# HBridge_GW.net
KiCad netlist of a schematic drawn in Altium Designer
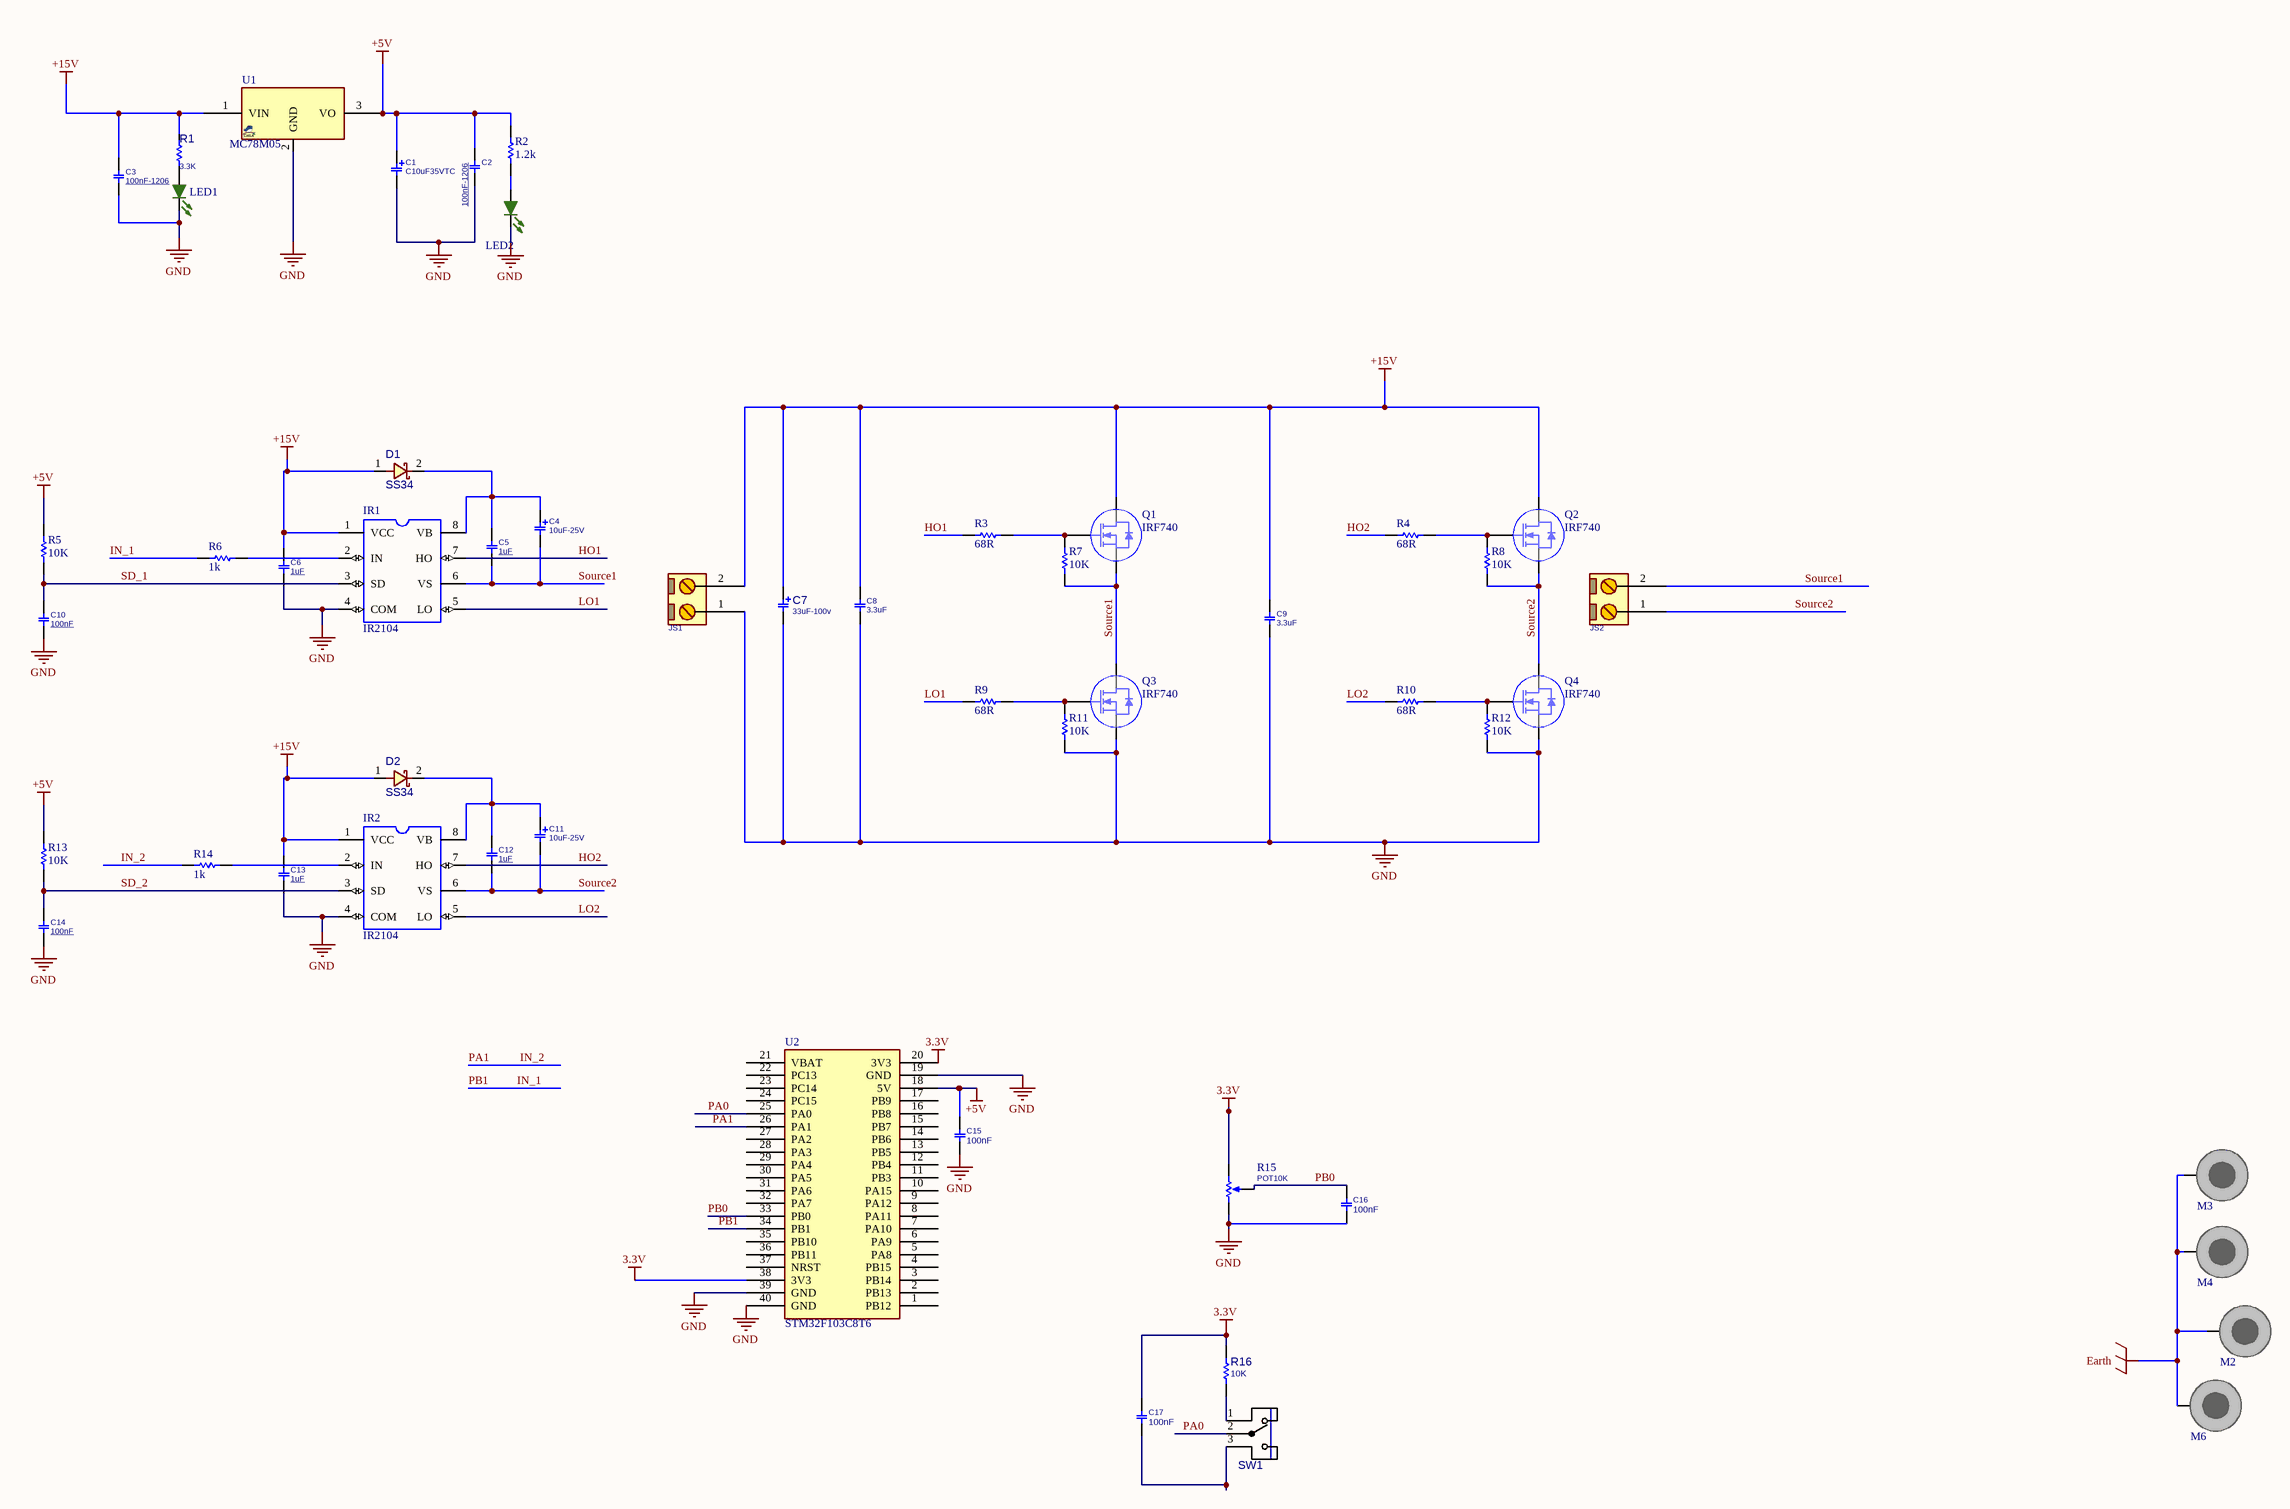
[diagram p0: HBridge_GW.SchDoc]

(export (version "E")
  (design (tool "Eeschema 10.0.6"))
  (components
    (comp (ref "C1")
      (value "C10uF35VTC")
      (footprint "C_TN_6032")
      (description "CAP, SMD, TAN,")
      (libsource (lib "passive_smd") (part "CAP_SMD_TAN_6032"))
    )
    (comp (ref "C2")
      (value "100nF-1206")
      (footprint "C1206")
      (description "CAP, MLCC, -F, -V, MATERIAL, -%, 0201")
      (fields (field (name "MANF_P#") "MANF_PART#"))
      (libsource (lib "passive_smd") (part "CAP_SMD_MLCC_1206"))
    )
    (comp (ref "C3")
      (value "100nF-1206")
      (footprint "C1206")
      (description "CAP, MLCC, -F, -V, MATERIAL, -%, 0201")
      (fields (field (name "MANF_P#") "MANF_PART#"))
      (libsource (lib "passive_smd") (part "CAP_SMD_MLCC_1206"))
    )
    (comp (ref "C4")
      (value "10uF-25V")
      (footprint "C_TN_3528")
      (description "CAP, SMD, TAN,")
      (libsource (lib "passive") (part "CAP_SMD_TAN"))
    )
    (comp (ref "C5")
      (value "1uF")
      (footprint "C1206")
      (description "CAP, MLCC, 1nF, 50V, C0G, 10%, 0402")
      (fields (field (name "MANF_P#") "MANF_PART#") (field (name "MANF") "Murata"))
      (libsource (lib "passive_smd") (part "CAP_SMD_MLCC"))
    )
    (comp (ref "C6")
      (value "1uF")
      (footprint "C1206")
      (description "CAP, MLCC, 1nF, 50V, C0G, 10%, 0402")
      (fields (field (name "MANF_P#") "MANF_PART#") (field (name "MANF") "Murata"))
      (libsource (lib "passive_smd") (part "CAP_SMD_MLCC"))
    )
    (comp (ref "C7")
      (value "33uF-100v")
      (footprint "C_EL_8X12")
      (description "CAP, THD, ELEC, 330uF, 25V")
      (fields (field (name "MANF_P#") "EEE-1EA331UP") (field (name "MANF") "PANASONIC"))
      (libsource (lib "CapElect_passive") (part "CAP_THD_EL_330u25V"))
    )
    (comp (ref "C8")
      (value "3.3uF")
      (footprint "C_PLY_13X5")
      (description "CAP, FILM, 10nF, 630V")
      (fields (field (name "MANF_P#") "MANF_PART#") (field (name "MANF") "MANF"))
      (libsource (lib "CapFilm_polyester_passive") (part "CAP_THD_FILMPLY_10N630V"))
    )
    (comp (ref "C9")
      (value "3.3uF")
      (footprint "C_PLY_13X5")
      (description "CAP, FILM, 10nF, 630V")
      (fields (field (name "MANF_P#") "MANF_PART#") (field (name "MANF") "MANF"))
      (libsource (lib "CapFilm_polyester_passive") (part "CAP_THD_FILMPLY_10N630V"))
    )
    (comp (ref "C10")
      (value "100nF")
      (footprint "C1206")
      (description "CAP, MLCC, 1nF, 50V, C0G, 10%, 0402")
      (fields (field (name "MANF_P#") "MANF_PART#") (field (name "MANF") "Murata"))
      (libsource (lib "passive_smd") (part "CAP_SMD_MLCC"))
    )
    (comp (ref "C11")
      (value "10uF-25V")
      (footprint "C_TN_3528")
      (description "CAP, SMD, TAN,")
      (libsource (lib "passive") (part "CAP_SMD_TAN"))
    )
    (comp (ref "C12")
      (value "1uF")
      (footprint "C1206")
      (description "CAP, MLCC, 1nF, 50V, C0G, 10%, 0402")
      (fields (field (name "MANF_P#") "MANF_PART#") (field (name "MANF") "Murata"))
      (libsource (lib "passive_smd") (part "CAP_SMD_MLCC"))
    )
    (comp (ref "C13")
      (value "1uF")
      (footprint "C1206")
      (description "CAP, MLCC, 1nF, 50V, C0G, 10%, 0402")
      (fields (field (name "MANF_P#") "MANF_PART#") (field (name "MANF") "Murata"))
      (libsource (lib "passive_smd") (part "CAP_SMD_MLCC"))
    )
    (comp (ref "C14")
      (value "100nF")
      (footprint "C1206")
      (description "CAP, MLCC, 1nF, 50V, C0G, 10%, 0402")
      (fields (field (name "MANF_P#") "MANF_PART#") (field (name "MANF") "Murata"))
      (libsource (lib "passive_smd") (part "CAP_SMD_MLCC"))
    )
    (comp (ref "C15")
      (value "100nF")
      (footprint "C1206")
      (description "CAP, MLCC")
      (fields (field (name "MANF_P#") "MANF_PART#"))
      (libsource (lib "passive_smd") (part "CAP_SMD_MLCC_1206"))
    )
    (comp (ref "C16")
      (value "100nF")
      (footprint "C1206")
      (description "CAP, MLCC")
      (fields (field (name "MANF_P#") "MANF_PART#"))
      (libsource (lib "passive_smd") (part "CAP_SMD_MLCC_1206"))
    )
    (comp (ref "C17")
      (value "100nF")
      (footprint "C1206")
      (description "CAP, MLCC")
      (fields (field (name "MANF_P#") "MANF_PART#"))
      (libsource (lib "passive_smd") (part "CAP_SMD_MLCC_1206"))
    )
    (comp (ref "D1")
      (value "SS34")
      (footprint "D_SMB")
      (description "DIODE, SCHOTTKY, 40V, 3A")
      (fields (field (name "MANF") "VISHAY"))
      (libsource (lib "diode") (part "DIODE_SMD_SCHOTTKY_SS34"))
    )
    (comp (ref "D2")
      (value "SS34")
      (footprint "D_SMB")
      (description "DIODE, SCHOTTKY, 40V, 3A")
      (fields (field (name "MANF") "VISHAY"))
      (libsource (lib "diode") (part "DIODE_SMD_SCHOTTKY_SS34"))
    )
    (comp (ref "IR1")
      (value "IR2104")
      (footprint "IR2104S")
      (description "Half-Bridge Gate Driver IC Non-Inverting")
      (fields (field (name "MP") "IR2104S") (field (name "MF") "Infineon Technologies"))
      (libsource (lib "IR2104S") (part "IR2104S"))
    )
    (comp (ref "IR2")
      (value "IR2104")
      (footprint "IR2104S")
      (description "Half-Bridge Gate Driver IC Non-Inverting")
      (fields (field (name "MP") "IR2104S") (field (name "MF") "Infineon Technologies"))
      (libsource (lib "IR2104S") (part "IR2104S"))
    )
    (comp (ref "JS1")
      (value "24V")
      (footprint "MSTB_2")
      (description "CONN, PHOENIX MSTB, 5-G, 5.08mm pitch")
      (libsource (lib "conn_power_terminalB") (part "CONN_MSTB_2"))
    )
    (comp (ref "JS2")
      (value "24V")
      (footprint "MSTB_2")
      (description "CONN, PHOENIX MSTB, 5-G, 5.08mm pitch")
      (libsource (lib "conn_power_terminalB") (part "CONN_MSTB_2"))
    )
    (comp (ref "LED1")
      (value "LED SMD 1206 GREEN")
      (footprint "IE_BuckProject:LED 1206 @")
      (libsource (lib "Schlib1") (part "LED SMD 1206 GREEN"))
    )
    (comp (ref "LED2")
      (value "LED SMD 1206 GREEN")
      (footprint "IE_BuckProject:LED 1206 @")
      (libsource (lib "Schlib1") (part "LED SMD 1206 GREEN"))
    )
    (comp (ref "M2")
      (value "DNP/MH")
      (footprint "SCMH_M3")
      (description "SCREW mouting, M3, 3.0mm diameter and 6.0mm PanHead")
      (libsource (lib "mech_mountingHole") (part "SCMH_M3"))
    )
    (comp (ref "M3")
      (value "DNP/MH")
      (footprint "SCMH_M3")
      (description "SCREW mouting, M3, 3.0mm diameter and 6.0mm PanHead")
      (libsource (lib "mech_mountingHole") (part "SCMH_M3"))
    )
    (comp (ref "M4")
      (value "DNP/MH")
      (footprint "SCMH_M3")
      (description "SCREW mouting, M3, 3.0mm diameter and 6.0mm PanHead")
      (libsource (lib "mech_mountingHole") (part "SCMH_M3"))
    )
    (comp (ref "M6")
      (value "DNP/MH")
      (footprint "SCMH_M3")
      (description "SCREW mouting, M3, 3.0mm diameter and 6.0mm PanHead")
      (libsource (lib "mech_mountingHole") (part "SCMH_M3"))
    )
    (comp (ref "Q1")
      (value "IRF740")
      (footprint "TO-220 AB")
      (description "MOSFET N-CH 400V 10A TO-220AB")
      (fields (field (name "PUBLISHER") "Abbas Basereh"))
      (libsource (lib "General 1") (part "IRF740"))
    )
    (comp (ref "Q2")
      (value "IRF740")
      (footprint "TO-220 AB")
      (description "MOSFET N-CH 400V 10A TO-220AB")
      (fields (field (name "PUBLISHER") "Abbas Basereh"))
      (libsource (lib "General 1") (part "IRF740"))
    )
    (comp (ref "Q3")
      (value "IRF740")
      (footprint "TO-220 AB")
      (description "MOSFET N-CH 400V 10A TO-220AB")
      (fields (field (name "PUBLISHER") "Abbas Basereh"))
      (libsource (lib "General 1") (part "IRF740"))
    )
    (comp (ref "Q4")
      (value "IRF740")
      (footprint "TO-220 AB")
      (description "MOSFET N-CH 400V 10A TO-220AB")
      (fields (field (name "PUBLISHER") "Abbas Basereh"))
      (libsource (lib "General 1") (part "IRF740"))
    )
    (comp (ref "R1")
      (value "3.3K")
      (footprint "RESC4817X04N")
      (description "RESISTOR, SMD")
      (fields (field (name "Comment") "RES_SMD") (field (name "DESIGNER") "ahmadi"))
      (libsource (lib "Schlib1") (part "RES_SMD"))
    )
    (comp (ref "R2")
      (value "1.2k")
      (footprint "RESC4817X04N")
      (description "RES 1206")
      (fields (field (name "DESIGNER") "Abbas Basereh"))
      (libsource (lib "2017AbbasBasereh9365731239 -ver1") (part "RES 1206 0.25W"))
    )
    (comp (ref "R3")
      (value "68R")
      (footprint "RESC4817X04N")
      (description "RES 1206")
      (fields (field (name "DESIGNER") "Abbas Basereh"))
      (libsource (lib "2017AbbasBasereh9365731239 -ver1") (part "RES 1206 0.25W"))
    )
    (comp (ref "R4")
      (value "68R")
      (footprint "RESC4817X04N")
      (description "RES 1206")
      (fields (field (name "DESIGNER") "Abbas Basereh"))
      (libsource (lib "2017AbbasBasereh9365731239 -ver1") (part "RES 1206 0.25W"))
    )
    (comp (ref "R5")
      (value "10K")
      (footprint "RESC4817X04N")
      (description "RES 1206")
      (fields (field (name "DESIGNER") "Abbas Basereh"))
      (libsource (lib "2017AbbasBasereh9365731239 -ver1") (part "RES 1206 0.25W"))
    )
    (comp (ref "R6")
      (value "1k")
      (footprint "RESC4817X04N")
      (description "RES 1206")
      (fields (field (name "DESIGNER") "Abbas Basereh"))
      (libsource (lib "2017AbbasBasereh9365731239 -ver1") (part "RES 1206 0.25W"))
    )
    (comp (ref "R7")
      (value "10K")
      (footprint "RESC4817X04N")
      (description "RES 1206")
      (fields (field (name "DESIGNER") "Abbas Basereh"))
      (libsource (lib "2017AbbasBasereh9365731239 -ver1") (part "RES 1206 0.25W"))
    )
    (comp (ref "R8")
      (value "10K")
      (footprint "RESC4817X04N")
      (description "RES 1206")
      (fields (field (name "DESIGNER") "Abbas Basereh"))
      (libsource (lib "2017AbbasBasereh9365731239 -ver1") (part "RES 1206 0.25W"))
    )
    (comp (ref "R9")
      (value "68R")
      (footprint "RESC4817X04N")
      (description "RES 1206")
      (fields (field (name "DESIGNER") "Abbas Basereh"))
      (libsource (lib "2017AbbasBasereh9365731239 -ver1") (part "RES 1206 0.25W"))
    )
    (comp (ref "R10")
      (value "68R")
      (footprint "RESC4817X04N")
      (description "RES 1206")
      (fields (field (name "DESIGNER") "Abbas Basereh"))
      (libsource (lib "2017AbbasBasereh9365731239 -ver1") (part "RES 1206 0.25W"))
    )
    (comp (ref "R11")
      (value "10K")
      (footprint "RESC4817X04N")
      (description "RES 1206")
      (fields (field (name "DESIGNER") "Abbas Basereh"))
      (libsource (lib "2017AbbasBasereh9365731239 -ver1") (part "RES 1206 0.25W"))
    )
    (comp (ref "R12")
      (value "10K")
      (footprint "RESC4817X04N")
      (description "RES 1206")
      (fields (field (name "DESIGNER") "Abbas Basereh"))
      (libsource (lib "2017AbbasBasereh9365731239 -ver1") (part "RES 1206 0.25W"))
    )
    (comp (ref "R13")
      (value "10K")
      (footprint "RESC4817X04N")
      (description "RES 1206")
      (fields (field (name "DESIGNER") "Abbas Basereh"))
      (libsource (lib "2017AbbasBasereh9365731239 -ver1") (part "RES 1206 0.25W"))
    )
    (comp (ref "R14")
      (value "1k")
      (footprint "RESC4817X04N")
      (description "RES 1206")
      (fields (field (name "DESIGNER") "Abbas Basereh"))
      (libsource (lib "2017AbbasBasereh9365731239 -ver1") (part "RES 1206 0.25W"))
    )
    (comp (ref "R15")
      (value "POT10K")
      (footprint "VOL_R")
      (description "RESISTOR, THD, Potentiometer Volume")
      (libsource (lib "resistor_pot_trimmer") (part "RES_THD_POT_VOLUME"))
    )
    (comp (ref "R16")
      (value "10K")
      (footprint "R1206")
      (description "RESISTOR, SMD")
      (libsource (lib "passive_smd") (part "RES_SMD_1206"))
    )
    (comp (ref "SW1")
      (value "ToggleSwitch")
      (footprint "SWTOG_SPDT_S_7101SY")
      (description "SWITCH, TOGGLE, SPDT, THD")
      (fields (field (name "MANF") "C&K") (field (name "MANF_PART#") "7101SYZBE"))
      (libsource (lib "switch_toggle") (part "SWTOG_SPDT_S_7101SY"))
    )
    (comp (ref "U1")
      (value "MC78M05")
      (footprint "TO220_3")
      (description "REG, Linear, Fixed, 5v, 1.5A, TO-220")
      (fields (field (name "MANF") "TI, ST, FAIRCHILD, ON, NJR, TS"))
      (libsource (lib "pwr_reg_linear_78xx79xx") (part "VREG_78M05_TO220"))
    )
    (comp (ref "U2")
      (value "STM32F103C8T6")
      (footprint "Stm32 BluePill")
      (description "Designed By @Alixahedi")
      (libsource (lib "Stm32 Blue Pill") (part "BluePill"))
    )
  )
  (nets
    (net (code "1") (name "+5V") (class "Default")
      (node (ref "C1") (pin "1") (pinfunction "1_1") (pintype "passive"))
      (node (ref "C15") (pin "2") (pinfunction "2_2") (pintype "passive"))
      (node (ref "C2") (pin "1") (pinfunction "1_1") (pintype "passive"))
      (node (ref "R13") (pin "2") (pinfunction "2_2") (pintype "passive"))
      (node (ref "R2") (pin "1") (pinfunction "1_1") (pintype "passive"))
      (node (ref "R5") (pin "2") (pinfunction "2_2") (pintype "passive"))
      (node (ref "U1") (pin "3") (pinfunction "VO_3") (pintype "passive"))
      (node (ref "U2") (pin "18") (pinfunction "5V_18") (pintype "passive"))
    )
    (net (code "2") (name "+15V") (class "Default")
      (node (ref "C13") (pin "2") (pinfunction "2_2") (pintype "passive"))
      (node (ref "C3") (pin "1") (pinfunction "1_1") (pintype "passive"))
      (node (ref "C6") (pin "2") (pinfunction "2_2") (pintype "passive"))
      (node (ref "C7") (pin "1") (pinfunction "1_1") (pintype "passive"))
      (node (ref "C8") (pin "2") (pinfunction "2_2") (pintype "passive"))
      (node (ref "C9") (pin "2") (pinfunction "2_2") (pintype "passive"))
      (node (ref "D1") (pin "1") (pinfunction "1_1") (pintype "passive"))
      (node (ref "D2") (pin "1") (pinfunction "1_1") (pintype "passive"))
      (node (ref "IR1") (pin "1") (pinfunction "VCC_1") (pintype "power_in"))
      (node (ref "IR2") (pin "1") (pinfunction "VCC_1") (pintype "power_in"))
      (node (ref "JS1") (pin "2") (pinfunction "2_2") (pintype "passive"))
      (node (ref "Q1") (pin "2") (pinfunction "D_2") (pintype "power_in"))
      (node (ref "Q2") (pin "2") (pinfunction "D_2") (pintype "power_in"))
      (node (ref "R1") (pin "1") (pinfunction "1_1") (pintype "passive"))
      (node (ref "U1") (pin "1") (pinfunction "VIN_1") (pintype "passive"))
    )
    (net (code "3") (name "/HO1") (class "Default")
      (node (ref "IR1") (pin "7") (pinfunction "HO_7") (pintype "bidirectional"))
      (node (ref "R3") (pin "2") (pinfunction "2_2") (pintype "passive"))
    )
    (net (code "4") (name "/HO2") (class "Default")
      (node (ref "IR2") (pin "7") (pinfunction "HO_7") (pintype "bidirectional"))
      (node (ref "R4") (pin "2") (pinfunction "2_2") (pintype "passive"))
    )
    (net (code "5") (name "/IN_1") (class "Default")
      (node (ref "R6") (pin "2") (pinfunction "2_2") (pintype "passive"))
      (node (ref "U2") (pin "34") (pinfunction "PB1_34") (pintype "passive"))
    )
    (net (code "6") (name "/IN_2") (class "Default")
      (node (ref "R14") (pin "2") (pinfunction "2_2") (pintype "passive"))
      (node (ref "U2") (pin "26") (pinfunction "PA1_26") (pintype "passive"))
    )
    (net (code "7") (name "/LO1") (class "Default")
      (node (ref "IR1") (pin "5") (pinfunction "LO_5") (pintype "bidirectional"))
      (node (ref "R9") (pin "2") (pinfunction "2_2") (pintype "passive"))
    )
    (net (code "8") (name "/LO2") (class "Default")
      (node (ref "IR2") (pin "5") (pinfunction "LO_5") (pintype "bidirectional"))
      (node (ref "R10") (pin "2") (pinfunction "2_2") (pintype "passive"))
    )
    (net (code "9") (name "/PA0") (class "Default")
      (node (ref "SW1") (pin "2") (pinfunction "COM_2") (pintype "passive"))
      (node (ref "U2") (pin "25") (pinfunction "PA0_25") (pintype "passive"))
    )
    (net (code "10") (name "/PB0") (class "Default")
      (node (ref "C16") (pin "2") (pinfunction "2_2") (pintype "passive"))
      (node (ref "R15") (pin "2") (pinfunction "TAP_2") (pintype "passive"))
      (node (ref "U2") (pin "33") (pinfunction "PB0_33") (pintype "passive"))
    )
    (net (code "11") (name "/SD_1") (class "Default")
      (node (ref "C10") (pin "2") (pinfunction "2_2") (pintype "passive"))
      (node (ref "IR1") (pin "3") (pinfunction "SD_3") (pintype "bidirectional"))
      (node (ref "R5") (pin "1") (pinfunction "1_1") (pintype "passive"))
    )
    (net (code "12") (name "/SD_2") (class "Default")
      (node (ref "C14") (pin "2") (pinfunction "2_2") (pintype "passive"))
      (node (ref "IR2") (pin "3") (pinfunction "SD_3") (pintype "bidirectional"))
      (node (ref "R13") (pin "1") (pinfunction "1_1") (pintype "passive"))
    )
    (net (code "13") (name "/Source1") (class "Default")
      (node (ref "C4") (pin "2") (pinfunction "2_2") (pintype "passive"))
      (node (ref "C5") (pin "1") (pinfunction "1_1") (pintype "passive"))
      (node (ref "IR1") (pin "6") (pinfunction "VS_6") (pintype "power_in"))
      (node (ref "JS2") (pin "2") (pinfunction "2_2") (pintype "passive"))
      (node (ref "Q1") (pin "3") (pinfunction "S_3") (pintype "power_in"))
      (node (ref "Q3") (pin "2") (pinfunction "D_2") (pintype "power_in"))
      (node (ref "R7") (pin "1") (pinfunction "1_1") (pintype "passive"))
    )
    (net (code "14") (name "/Source2") (class "Default")
      (node (ref "C11") (pin "2") (pinfunction "2_2") (pintype "passive"))
      (node (ref "C12") (pin "1") (pinfunction "1_1") (pintype "passive"))
      (node (ref "IR2") (pin "6") (pinfunction "VS_6") (pintype "power_in"))
      (node (ref "JS2") (pin "1") (pinfunction "1_1") (pintype "passive"))
      (node (ref "Q2") (pin "3") (pinfunction "S_3") (pintype "power_in"))
      (node (ref "Q4") (pin "2") (pinfunction "D_2") (pintype "power_in"))
      (node (ref "R8") (pin "1") (pinfunction "1_1") (pintype "passive"))
    )
    (net (code "15") (name "3.3V") (class "Default")
      (node (ref "C17") (pin "1") (pinfunction "1_1") (pintype "passive"))
      (node (ref "R15") (pin "3") (pinfunction "BOT_3") (pintype "passive"))
      (node (ref "R16") (pin "2") (pinfunction "2_2") (pintype "passive"))
      (node (ref "U2") (pin "20") (pinfunction "3V3_20") (pintype "passive"))
      (node (ref "U2") (pin "38") (pinfunction "3V3_38") (pintype "passive"))
    )
    (net (code "16") (name "Earth") (class "Default")
      (node (ref "M2") (pin "1") (pinfunction "1_1") (pintype "passive"))
      (node (ref "M3") (pin "1") (pinfunction "1_1") (pintype "passive"))
      (node (ref "M4") (pin "1") (pinfunction "1_1") (pintype "passive"))
      (node (ref "M6") (pin "1") (pinfunction "1_1") (pintype "passive"))
    )
    (net (code "17") (name "GND") (class "Default")
      (node (ref "C1") (pin "2") (pinfunction "2_2") (pintype "passive"))
      (node (ref "C10") (pin "1") (pinfunction "1_1") (pintype "passive"))
      (node (ref "C13") (pin "1") (pinfunction "1_1") (pintype "passive"))
      (node (ref "C14") (pin "1") (pinfunction "1_1") (pintype "passive"))
      (node (ref "C15") (pin "1") (pinfunction "1_1") (pintype "passive"))
      (node (ref "C16") (pin "1") (pinfunction "1_1") (pintype "passive"))
      (node (ref "C2") (pin "2") (pinfunction "2_2") (pintype "passive"))
      (node (ref "C3") (pin "2") (pinfunction "2_2") (pintype "passive"))
      (node (ref "C6") (pin "1") (pinfunction "1_1") (pintype "passive"))
      (node (ref "C7") (pin "2") (pinfunction "2_2") (pintype "passive"))
      (node (ref "C8") (pin "1") (pinfunction "1_1") (pintype "passive"))
      (node (ref "C9") (pin "1") (pinfunction "1_1") (pintype "passive"))
      (node (ref "IR1") (pin "4") (pinfunction "COM_4") (pintype "bidirectional"))
      (node (ref "IR2") (pin "4") (pinfunction "COM_4") (pintype "bidirectional"))
      (node (ref "JS1") (pin "1") (pinfunction "1_1") (pintype "passive"))
      (node (ref "LED1") (pin "2") (pinfunction "K_2") (pintype "passive"))
      (node (ref "LED2") (pin "2") (pinfunction "K_2") (pintype "passive"))
      (node (ref "Q3") (pin "3") (pinfunction "S_3") (pintype "power_in"))
      (node (ref "Q4") (pin "3") (pinfunction "S_3") (pintype "power_in"))
      (node (ref "R11") (pin "1") (pinfunction "1_1") (pintype "passive"))
      (node (ref "R12") (pin "1") (pinfunction "1_1") (pintype "passive"))
      (node (ref "R15") (pin "1") (pinfunction "TOP_1") (pintype "passive"))
      (node (ref "U1") (pin "2") (pinfunction "GND_2") (pintype "passive"))
      (node (ref "U2") (pin "19") (pinfunction "GND_19") (pintype "passive"))
      (node (ref "U2") (pin "39") (pinfunction "GND_39") (pintype "passive"))
      (node (ref "U2") (pin "40") (pinfunction "GND_40") (pintype "passive"))
    )
    (net (code "18") (name "Net-(IR1-IN)") (class "Default")
      (node (ref "IR1") (pin "2") (pinfunction "IN_2") (pintype "bidirectional"))
      (node (ref "R6") (pin "1") (pinfunction "1_1") (pintype "passive"))
    )
    (net (code "19") (name "Net-(IR1-VB)") (class "Default")
      (node (ref "C4") (pin "1") (pinfunction "1_1") (pintype "passive"))
      (node (ref "C5") (pin "2") (pinfunction "2_2") (pintype "passive"))
      (node (ref "D1") (pin "2") (pinfunction "2_2") (pintype "passive"))
      (node (ref "IR1") (pin "8") (pinfunction "VB_8") (pintype "power_in"))
    )
    (net (code "20") (name "Net-(IR2-IN)") (class "Default")
      (node (ref "IR2") (pin "2") (pinfunction "IN_2") (pintype "bidirectional"))
      (node (ref "R14") (pin "1") (pinfunction "1_1") (pintype "passive"))
    )
    (net (code "21") (name "Net-(IR2-VB)") (class "Default")
      (node (ref "C11") (pin "1") (pinfunction "1_1") (pintype "passive"))
      (node (ref "C12") (pin "2") (pinfunction "2_2") (pintype "passive"))
      (node (ref "D2") (pin "2") (pinfunction "2_2") (pintype "passive"))
      (node (ref "IR2") (pin "8") (pinfunction "VB_8") (pintype "power_in"))
    )
    (net (code "22") (name "Net-(LED1-A)") (class "Default")
      (node (ref "LED1") (pin "1") (pinfunction "A_1") (pintype "passive"))
      (node (ref "R1") (pin "2") (pinfunction "2_2") (pintype "passive"))
    )
    (net (code "23") (name "Net-(LED2-A)") (class "Default")
      (node (ref "LED2") (pin "1") (pinfunction "A_1") (pintype "passive"))
      (node (ref "R2") (pin "2") (pinfunction "2_2") (pintype "passive"))
    )
    (net (code "24") (name "Net-(Q1-G)") (class "Default")
      (node (ref "Q1") (pin "1") (pinfunction "G_1") (pintype "passive"))
      (node (ref "R3") (pin "1") (pinfunction "1_1") (pintype "passive"))
      (node (ref "R7") (pin "2") (pinfunction "2_2") (pintype "passive"))
    )
    (net (code "25") (name "Net-(Q2-G)") (class "Default")
      (node (ref "Q2") (pin "1") (pinfunction "G_1") (pintype "passive"))
      (node (ref "R4") (pin "1") (pinfunction "1_1") (pintype "passive"))
      (node (ref "R8") (pin "2") (pinfunction "2_2") (pintype "passive"))
    )
    (net (code "26") (name "Net-(Q3-G)") (class "Default")
      (node (ref "Q3") (pin "1") (pinfunction "G_1") (pintype "passive"))
      (node (ref "R11") (pin "2") (pinfunction "2_2") (pintype "passive"))
      (node (ref "R9") (pin "1") (pinfunction "1_1") (pintype "passive"))
    )
    (net (code "27") (name "Net-(Q4-G)") (class "Default")
      (node (ref "Q4") (pin "1") (pinfunction "G_1") (pintype "passive"))
      (node (ref "R10") (pin "1") (pinfunction "1_1") (pintype "passive"))
      (node (ref "R12") (pin "2") (pinfunction "2_2") (pintype "passive"))
    )
    (net (code "28") (name "Net-(SW1-T1)") (class "Default")
      (node (ref "R16") (pin "1") (pinfunction "1_1") (pintype "passive"))
      (node (ref "SW1") (pin "1") (pinfunction "T1_1") (pintype "passive"))
    )
    (net (code "29") (name "Net-(SW1-T2)") (class "Default")
      (node (ref "C17") (pin "2") (pinfunction "2_2") (pintype "passive"))
      (node (ref "SW1") (pin "3") (pinfunction "T2_3") (pintype "passive"))
    )
    (net (code "30") (name "unconnected-(U2-NRST-Pad37)") (class "Default")
      (node (ref "U2") (pin "37") (pinfunction "NRST_37") (pintype "passive"))
    )
    (net (code "31") (name "unconnected-(U2-PA2-Pad27)") (class "Default")
      (node (ref "U2") (pin "27") (pinfunction "PA2_27") (pintype "passive"))
    )
    (net (code "32") (name "unconnected-(U2-PA3-Pad28)") (class "Default")
      (node (ref "U2") (pin "28") (pinfunction "PA3_28") (pintype "passive"))
    )
    (net (code "33") (name "unconnected-(U2-PA4-Pad29)") (class "Default")
      (node (ref "U2") (pin "29") (pinfunction "PA4_29") (pintype "passive"))
    )
    (net (code "34") (name "unconnected-(U2-PA5-Pad30)") (class "Default")
      (node (ref "U2") (pin "30") (pinfunction "PA5_30") (pintype "passive"))
    )
    (net (code "35") (name "unconnected-(U2-PA6-Pad31)") (class "Default")
      (node (ref "U2") (pin "31") (pinfunction "PA6_31") (pintype "passive"))
    )
    (net (code "36") (name "unconnected-(U2-PA7-Pad32)") (class "Default")
      (node (ref "U2") (pin "32") (pinfunction "PA7_32") (pintype "passive"))
    )
    (net (code "37") (name "unconnected-(U2-PA8-Pad5)") (class "Default")
      (node (ref "U2") (pin "5") (pinfunction "PA8_5") (pintype "passive"))
    )
    (net (code "38") (name "unconnected-(U2-PA9-Pad6)") (class "Default")
      (node (ref "U2") (pin "6") (pinfunction "PA9_6") (pintype "passive"))
    )
    (net (code "39") (name "unconnected-(U2-PA10-Pad7)") (class "Default")
      (node (ref "U2") (pin "7") (pinfunction "PA10_7") (pintype "passive"))
    )
    (net (code "40") (name "unconnected-(U2-PA11-Pad8)") (class "Default")
      (node (ref "U2") (pin "8") (pinfunction "PA11_8") (pintype "passive"))
    )
    (net (code "41") (name "unconnected-(U2-PA12-Pad9)") (class "Default")
      (node (ref "U2") (pin "9") (pinfunction "PA12_9") (pintype "passive"))
    )
    (net (code "42") (name "unconnected-(U2-PA15-Pad10)") (class "Default")
      (node (ref "U2") (pin "10") (pinfunction "PA15_10") (pintype "passive"))
    )
    (net (code "43") (name "unconnected-(U2-PB3-Pad11)") (class "Default")
      (node (ref "U2") (pin "11") (pinfunction "PB3_11") (pintype "passive"))
    )
    (net (code "44") (name "unconnected-(U2-PB4-Pad12)") (class "Default")
      (node (ref "U2") (pin "12") (pinfunction "PB4_12") (pintype "passive"))
    )
    (net (code "45") (name "unconnected-(U2-PB5-Pad13)") (class "Default")
      (node (ref "U2") (pin "13") (pinfunction "PB5_13") (pintype "passive"))
    )
    (net (code "46") (name "unconnected-(U2-PB6-Pad14)") (class "Default")
      (node (ref "U2") (pin "14") (pinfunction "PB6_14") (pintype "passive"))
    )
    (net (code "47") (name "unconnected-(U2-PB7-Pad15)") (class "Default")
      (node (ref "U2") (pin "15") (pinfunction "PB7_15") (pintype "passive"))
    )
    (net (code "48") (name "unconnected-(U2-PB8-Pad16)") (class "Default")
      (node (ref "U2") (pin "16") (pinfunction "PB8_16") (pintype "passive"))
    )
    (net (code "49") (name "unconnected-(U2-PB9-Pad17)") (class "Default")
      (node (ref "U2") (pin "17") (pinfunction "PB9_17") (pintype "passive"))
    )
    (net (code "50") (name "unconnected-(U2-PB10-Pad35)") (class "Default")
      (node (ref "U2") (pin "35") (pinfunction "PB10_35") (pintype "passive"))
    )
    (net (code "51") (name "unconnected-(U2-PB11-Pad36)") (class "Default")
      (node (ref "U2") (pin "36") (pinfunction "PB11_36") (pintype "passive"))
    )
    (net (code "52") (name "unconnected-(U2-PB12-Pad1)") (class "Default")
      (node (ref "U2") (pin "1") (pinfunction "PB12_1") (pintype "passive"))
    )
    (net (code "53") (name "unconnected-(U2-PB13-Pad2)") (class "Default")
      (node (ref "U2") (pin "2") (pinfunction "PB13_2") (pintype "passive"))
    )
    (net (code "54") (name "unconnected-(U2-PB14-Pad3)") (class "Default")
      (node (ref "U2") (pin "3") (pinfunction "PB14_3") (pintype "passive"))
    )
    (net (code "55") (name "unconnected-(U2-PB15-Pad4)") (class "Default")
      (node (ref "U2") (pin "4") (pinfunction "PB15_4") (pintype "passive"))
    )
    (net (code "56") (name "unconnected-(U2-PC13-Pad22)") (class "Default")
      (node (ref "U2") (pin "22") (pinfunction "PC13_22") (pintype "passive"))
    )
    (net (code "57") (name "unconnected-(U2-PC14-Pad23)") (class "Default")
      (node (ref "U2") (pin "23") (pinfunction "PC14_23") (pintype "passive"))
    )
    (net (code "58") (name "unconnected-(U2-PC15-Pad24)") (class "Default")
      (node (ref "U2") (pin "24") (pinfunction "PC15_24") (pintype "passive"))
    )
    (net (code "59") (name "unconnected-(U2-VBAT-Pad21)") (class "Default")
      (node (ref "U2") (pin "21") (pinfunction "VBAT_21") (pintype "passive"))
    )
  )
)
